# FreedomWingSMD.net
KiCad netlist of a schematic drawn in EAGLE
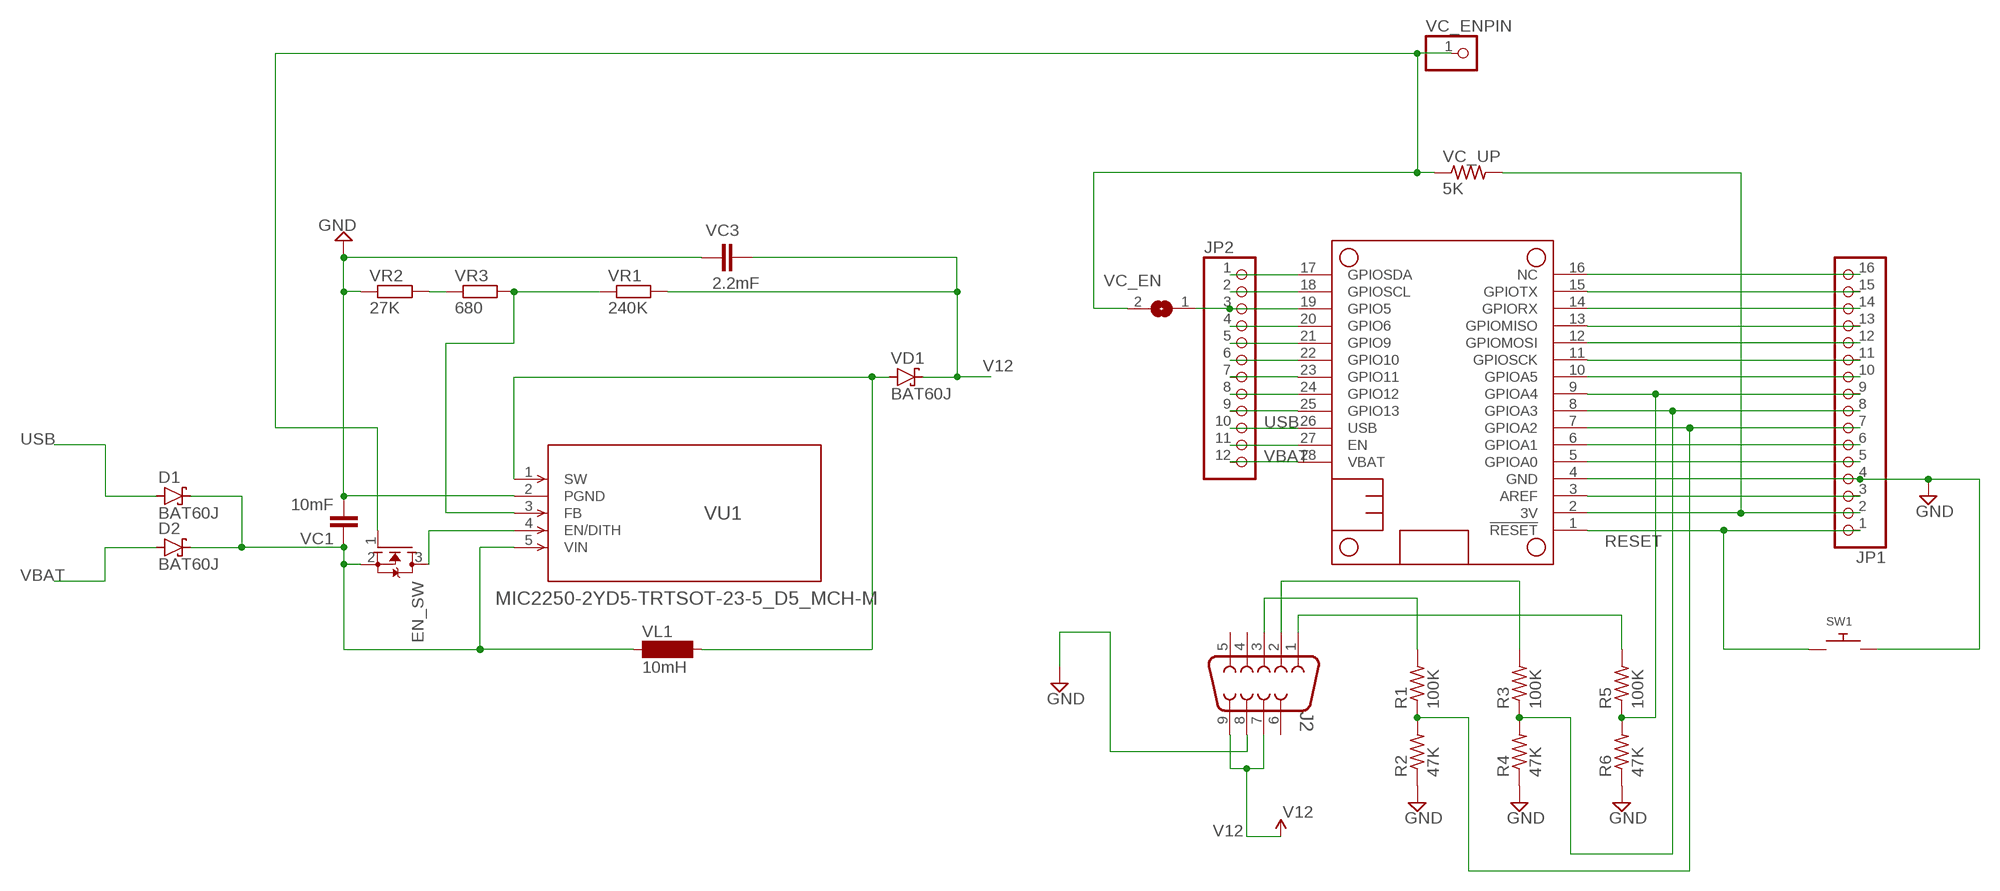
[diagram p0: schematic, sheet 1]

(export (version "E")
  (design (tool "Eeschema 10.0.6"))
  (components
    (comp (ref "D1")
      (value "BAT60J")
      (footprint "eagle-import:SOD323_ST")
      (libsource (lib "eagle-import") (part "BAT60J"))
    )
    (comp (ref "D2")
      (value "BAT60J")
      (footprint "eagle-import:SOD323_ST")
      (libsource (lib "eagle-import") (part "BAT60J"))
    )
    (comp (ref "EN_SW")
      (value "MOSFET-NREFLOW")
      (footprint "eagle-import:SOT23")
      (libsource (lib "eagle-import") (part "MOSFET-NREFLOW"))
    )
    (comp (ref "J2")
      (value "DB9MALE")
      (footprint "eagle-import:DB9_MALE")
      (libsource (lib "eagle-import") (part "DB9MALE"))
    )
    (comp (ref "JP1")
      (value "PINHD-1X16")
      (footprint "eagle-import:1X16")
      (libsource (lib "eagle-import") (part "PINHD-1X16"))
    )
    (comp (ref "JP2")
      (value "PINHD-1X12")
      (footprint "eagle-import:1X12")
      (libsource (lib "eagle-import") (part "PINHD-1X12"))
    )
    (comp (ref "MS1")
      (value "FEATHERWING_NODIM")
      (footprint "eagle-import:FEATHERWING_DIM")
      (libsource (lib "eagle-import") (part "FEATHERWING_NODIM"))
    )
    (comp (ref "R1")
      (value "100K")
      (footprint "eagle-import:R0805")
      (libsource (lib "eagle-import") (part "adafruit_420_R-US_R0805"))
    )
    (comp (ref "R2")
      (value "47K")
      (footprint "eagle-import:R0805")
      (libsource (lib "eagle-import") (part "adafruit_420_R-US_R0805"))
    )
    (comp (ref "R3")
      (value "100K")
      (footprint "eagle-import:R0805")
      (libsource (lib "eagle-import") (part "adafruit_420_R-US_R0805"))
    )
    (comp (ref "R4")
      (value "47K")
      (footprint "eagle-import:R0805")
      (libsource (lib "eagle-import") (part "adafruit_420_R-US_R0805"))
    )
    (comp (ref "R5")
      (value "100K")
      (footprint "eagle-import:R0805")
      (libsource (lib "eagle-import") (part "adafruit_420_R-US_R0805"))
    )
    (comp (ref "R6")
      (value "47K")
      (footprint "eagle-import:R0805")
      (libsource (lib "eagle-import") (part "adafruit_420_R-US_R0805"))
    )
    (comp (ref "SW1")
      (value "SWITCH_PUSHBUTTONC&K_KSS")
      (footprint "eagle-import:BTN_CK_KSS")
      (libsource (lib "eagle-import") (part "SWITCH_PUSHBUTTONC&K_KSS"))
    )
    (comp (ref "VC1")
      (value "10mF")
      (footprint "eagle-import:C0805")
      (libsource (lib "eagle-import") (part "C-EUC0805"))
    )
    (comp (ref "VC3")
      (value "2.2mF")
      (footprint "eagle-import:C0805")
      (libsource (lib "eagle-import") (part "C-EUC0805"))
    )
    (comp (ref "VC_EN")
      (value "SJW")
      (footprint "eagle-import:SJW")
      (libsource (lib "eagle-import") (part "SJW"))
    )
    (comp (ref "VC_ENPIN")
      (value "PINHD-1X1")
      (footprint "eagle-import:1X01")
      (libsource (lib "eagle-import") (part "PINHD-1X1"))
    )
    (comp (ref "VC_UP")
      (value "5K")
      (footprint "eagle-import:R0805")
      (libsource (lib "eagle-import") (part "R-US_R0805"))
    )
    (comp (ref "VD1")
      (value "BAT60J")
      (footprint "eagle-import:SOD323_ST")
      (libsource (lib "eagle-import") (part "BAT60J"))
    )
    (comp (ref "VL1")
      (value "10mH")
      (footprint "eagle-import:MS50")
      (libsource (lib "eagle-import") (part "MS50"))
    )
    (comp (ref "VR1")
      (value "240K")
      (footprint "eagle-import:R0805W")
      (libsource (lib "eagle-import") (part "R-EU_R0805W"))
    )
    (comp (ref "VR2")
      (value "27K")
      (footprint "eagle-import:R0805W")
      (libsource (lib "eagle-import") (part "R-EU_R0805W"))
    )
    (comp (ref "VR3")
      (value "680")
      (footprint "eagle-import:R0805W")
      (libsource (lib "eagle-import") (part "R-EU_R0805W"))
    )
    (comp (ref "VU1")
      (value "MIC2250-2YD5-TRTSOT-23-5_D5_MCH-M")
      (footprint "eagle-import:TSOT-23-5_D5_MCH-M")
      (fields
        (field (name "MANUFACTURER_PART_NUMBER") "MIC2250-2YD5-TR")
        (field (name "COPYRIGHT") "Copyright (C) 2018 Accelerated Designs. All rights reserved")
      )
      (libsource (lib "eagle-import") (part "MIC2250-2YD5-TRTSOT-23-5_D5_MCH-M"))
    )
  )
  (nets
    (net (code "1") (name "/RESET") (class "Default")
      (node (ref "JP1") (pin "1") (pinfunction "1_1") (pintype "passive"))
      (node (ref "MS1") (pin "1") (pinfunction "~{RESET}_1") (pintype "input"))
      (node (ref "SW1") (pin "P$1") (pinfunction "P$1_P$1") (pintype "passive"))
    )
    (net (code "2") (name "/USB") (class "Default")
      (node (ref "D1") (pin "A") (pinfunction "A_A") (pintype "passive"))
      (node (ref "JP2") (pin "10") (pinfunction "10_10") (pintype "passive"))
      (node (ref "MS1") (pin "26") (pinfunction "USB_26") (pintype "power_in"))
    )
    (net (code "3") (name "/VBAT") (class "Default")
      (node (ref "D2") (pin "A") (pinfunction "A_A") (pintype "passive"))
      (node (ref "JP2") (pin "12") (pinfunction "12_12") (pintype "passive"))
      (node (ref "MS1") (pin "28") (pinfunction "VBAT_28") (pintype "power_in"))
    )
    (net (code "4") (name "GND") (class "Default")
      (node (ref "J2") (pin "8") (pinfunction "8_8") (pintype "passive"))
      (node (ref "JP1") (pin "4") (pinfunction "4_4") (pintype "passive"))
      (node (ref "MS1") (pin "4") (pinfunction "GND_4") (pintype "power_in"))
      (node (ref "R2") (pin "1") (pinfunction "1_1") (pintype "passive"))
      (node (ref "R4") (pin "1") (pinfunction "1_1") (pintype "passive"))
      (node (ref "R6") (pin "1") (pinfunction "1_1") (pintype "passive"))
      (node (ref "SW1") (pin "P$2") (pinfunction "P$2_P$2") (pintype "passive"))
      (node (ref "VC1") (pin "2") (pinfunction "2_2") (pintype "passive"))
      (node (ref "VC3") (pin "1") (pinfunction "1_1") (pintype "passive"))
      (node (ref "VR2") (pin "1") (pinfunction "1_1") (pintype "passive"))
      (node (ref "VU1") (pin "2") (pinfunction "PGND_2") (pintype "power_in"))
    )
    (net (code "5") (name "Net-(EN_SW-D)") (class "Default")
      (node (ref "EN_SW") (pin "3") (pinfunction "D_3") (pintype "bidirectional"))
      (node (ref "VU1") (pin "4") (pinfunction "EN/DITH_4") (pintype "input"))
    )
    (net (code "6") (name "Net-(EN_SW-G)") (class "Default")
      (node (ref "EN_SW") (pin "1") (pinfunction "G_1") (pintype "bidirectional"))
      (node (ref "VC_EN") (pin "2") (pinfunction "2_2") (pintype "passive"))
      (node (ref "VC_ENPIN") (pin "1") (pinfunction "1_1") (pintype "passive"))
      (node (ref "VC_UP") (pin "1") (pinfunction "1_1") (pintype "passive"))
    )
    (net (code "7") (name "Net-(EN_SW-S)") (class "Default")
      (node (ref "D1") (pin "C") (pinfunction "C_C") (pintype "passive"))
      (node (ref "D2") (pin "C") (pinfunction "C_C") (pintype "passive"))
      (node (ref "EN_SW") (pin "2") (pinfunction "S_2") (pintype "bidirectional"))
      (node (ref "VC1") (pin "1") (pinfunction "1_1") (pintype "passive"))
      (node (ref "VL1") (pin "1") (pinfunction "1_1") (pintype "passive"))
      (node (ref "VU1") (pin "5") (pinfunction "VIN_5") (pintype "input"))
    )
    (net (code "8") (name "Net-(J2-Pad1)") (class "Default")
      (node (ref "J2") (pin "1") (pinfunction "1_1") (pintype "passive"))
      (node (ref "R5") (pin "2") (pinfunction "2_2") (pintype "passive"))
    )
    (net (code "9") (name "Net-(J2-Pad2)") (class "Default")
      (node (ref "J2") (pin "2") (pinfunction "2_2") (pintype "passive"))
      (node (ref "R3") (pin "2") (pinfunction "2_2") (pintype "passive"))
    )
    (net (code "10") (name "Net-(J2-Pad3)") (class "Default")
      (node (ref "J2") (pin "3") (pinfunction "3_3") (pintype "passive"))
      (node (ref "R1") (pin "2") (pinfunction "2_2") (pintype "passive"))
    )
    (net (code "11") (name "Net-(MS1-3V)") (class "Default")
      (node (ref "JP1") (pin "2") (pinfunction "2_2") (pintype "passive"))
      (node (ref "MS1") (pin "2") (pinfunction "3V_2") (pintype "power_in"))
      (node (ref "VC_UP") (pin "2") (pinfunction "2_2") (pintype "passive"))
    )
    (net (code "12") (name "Net-(MS1-AREF)") (class "Default")
      (node (ref "JP1") (pin "3") (pinfunction "3_3") (pintype "passive"))
      (node (ref "MS1") (pin "3") (pinfunction "AREF_3") (pintype "passive"))
    )
    (net (code "13") (name "Net-(MS1-EN)") (class "Default")
      (node (ref "JP2") (pin "11") (pinfunction "11_11") (pintype "passive"))
      (node (ref "MS1") (pin "27") (pinfunction "EN_27") (pintype "passive"))
    )
    (net (code "14") (name "Net-(MS1-GPIO5)") (class "Default")
      (node (ref "JP2") (pin "3") (pinfunction "3_3") (pintype "passive"))
      (node (ref "MS1") (pin "19") (pinfunction "GPIO5_19") (pintype "bidirectional"))
      (node (ref "VC_EN") (pin "1") (pinfunction "1_1") (pintype "passive"))
    )
    (net (code "15") (name "Net-(MS1-GPIO6)") (class "Default")
      (node (ref "JP2") (pin "4") (pinfunction "4_4") (pintype "passive"))
      (node (ref "MS1") (pin "20") (pinfunction "GPIO6_20") (pintype "bidirectional"))
    )
    (net (code "16") (name "Net-(MS1-GPIO9)") (class "Default")
      (node (ref "JP2") (pin "5") (pinfunction "5_5") (pintype "passive"))
      (node (ref "MS1") (pin "21") (pinfunction "GPIO9_21") (pintype "bidirectional"))
    )
    (net (code "17") (name "Net-(MS1-GPIO10)") (class "Default")
      (node (ref "JP2") (pin "6") (pinfunction "6_6") (pintype "passive"))
      (node (ref "MS1") (pin "22") (pinfunction "GPIO10_22") (pintype "bidirectional"))
    )
    (net (code "18") (name "Net-(MS1-GPIO11)") (class "Default")
      (node (ref "JP2") (pin "7") (pinfunction "7_7") (pintype "passive"))
      (node (ref "MS1") (pin "23") (pinfunction "GPIO11_23") (pintype "bidirectional"))
    )
    (net (code "19") (name "Net-(MS1-GPIO12)") (class "Default")
      (node (ref "JP2") (pin "8") (pinfunction "8_8") (pintype "passive"))
      (node (ref "MS1") (pin "24") (pinfunction "GPIO12_24") (pintype "bidirectional"))
    )
    (net (code "20") (name "Net-(MS1-GPIO13)") (class "Default")
      (node (ref "JP2") (pin "9") (pinfunction "9_9") (pintype "passive"))
      (node (ref "MS1") (pin "25") (pinfunction "GPIO13_25") (pintype "bidirectional"))
    )
    (net (code "21") (name "Net-(MS1-GPIOA0)") (class "Default")
      (node (ref "JP1") (pin "5") (pinfunction "5_5") (pintype "passive"))
      (node (ref "MS1") (pin "5") (pinfunction "GPIOA0_5") (pintype "bidirectional"))
    )
    (net (code "22") (name "Net-(MS1-GPIOA1)") (class "Default")
      (node (ref "JP1") (pin "6") (pinfunction "6_6") (pintype "passive"))
      (node (ref "MS1") (pin "6") (pinfunction "GPIOA1_6") (pintype "bidirectional"))
    )
    (net (code "23") (name "Net-(MS1-GPIOA2)") (class "Default")
      (node (ref "JP1") (pin "7") (pinfunction "7_7") (pintype "passive"))
      (node (ref "MS1") (pin "7") (pinfunction "GPIOA2_7") (pintype "bidirectional"))
      (node (ref "R1") (pin "1") (pinfunction "1_1") (pintype "passive"))
      (node (ref "R2") (pin "2") (pinfunction "2_2") (pintype "passive"))
    )
    (net (code "24") (name "Net-(MS1-GPIOA3)") (class "Default")
      (node (ref "JP1") (pin "8") (pinfunction "8_8") (pintype "passive"))
      (node (ref "MS1") (pin "8") (pinfunction "GPIOA3_8") (pintype "bidirectional"))
      (node (ref "R3") (pin "1") (pinfunction "1_1") (pintype "passive"))
      (node (ref "R4") (pin "2") (pinfunction "2_2") (pintype "passive"))
    )
    (net (code "25") (name "Net-(MS1-GPIOA4)") (class "Default")
      (node (ref "JP1") (pin "9") (pinfunction "9_9") (pintype "passive"))
      (node (ref "MS1") (pin "9") (pinfunction "GPIOA4_9") (pintype "bidirectional"))
      (node (ref "R5") (pin "1") (pinfunction "1_1") (pintype "passive"))
      (node (ref "R6") (pin "2") (pinfunction "2_2") (pintype "passive"))
    )
    (net (code "26") (name "Net-(MS1-GPIOA5)") (class "Default")
      (node (ref "JP1") (pin "10") (pinfunction "10_10") (pintype "passive"))
      (node (ref "MS1") (pin "10") (pinfunction "GPIOA5_10") (pintype "bidirectional"))
    )
    (net (code "27") (name "Net-(MS1-GPIOMISO)") (class "Default")
      (node (ref "JP1") (pin "13") (pinfunction "13_13") (pintype "passive"))
      (node (ref "MS1") (pin "13") (pinfunction "GPIOMISO_13") (pintype "bidirectional"))
    )
    (net (code "28") (name "Net-(MS1-GPIOMOSI)") (class "Default")
      (node (ref "JP1") (pin "12") (pinfunction "12_12") (pintype "passive"))
      (node (ref "MS1") (pin "12") (pinfunction "GPIOMOSI_12") (pintype "bidirectional"))
    )
    (net (code "29") (name "Net-(MS1-GPIORX)") (class "Default")
      (node (ref "JP1") (pin "14") (pinfunction "14_14") (pintype "passive"))
      (node (ref "MS1") (pin "14") (pinfunction "GPIORX_14") (pintype "bidirectional"))
    )
    (net (code "30") (name "Net-(MS1-GPIOSCK)") (class "Default")
      (node (ref "JP1") (pin "11") (pinfunction "11_11") (pintype "passive"))
      (node (ref "MS1") (pin "11") (pinfunction "GPIOSCK_11") (pintype "bidirectional"))
    )
    (net (code "31") (name "Net-(MS1-GPIOSCL)") (class "Default")
      (node (ref "JP2") (pin "2") (pinfunction "2_2") (pintype "passive"))
      (node (ref "MS1") (pin "18") (pinfunction "GPIOSCL_18") (pintype "bidirectional"))
    )
    (net (code "32") (name "Net-(MS1-GPIOSDA)") (class "Default")
      (node (ref "JP2") (pin "1") (pinfunction "1_1") (pintype "passive"))
      (node (ref "MS1") (pin "17") (pinfunction "GPIOSDA_17") (pintype "bidirectional"))
    )
    (net (code "33") (name "Net-(MS1-GPIOTX)") (class "Default")
      (node (ref "JP1") (pin "15") (pinfunction "15_15") (pintype "passive"))
      (node (ref "MS1") (pin "15") (pinfunction "GPIOTX_15") (pintype "bidirectional"))
    )
    (net (code "34") (name "Net-(MS1-NC)") (class "Default")
      (node (ref "JP1") (pin "16") (pinfunction "16_16") (pintype "passive"))
      (node (ref "MS1") (pin "16") (pinfunction "NC_16") (pintype "passive"))
    )
    (net (code "35") (name "Net-(VR2-Pad2)") (class "Default")
      (node (ref "VR2") (pin "2") (pinfunction "2_2") (pintype "passive"))
      (node (ref "VR3") (pin "1") (pinfunction "1_1") (pintype "passive"))
    )
    (net (code "36") (name "Net-(VU1-FB)") (class "Default")
      (node (ref "VR1") (pin "1") (pinfunction "1_1") (pintype "passive"))
      (node (ref "VR3") (pin "2") (pinfunction "2_2") (pintype "passive"))
      (node (ref "VU1") (pin "3") (pinfunction "FB_3") (pintype "input"))
    )
    (net (code "37") (name "Net-(VU1-SW)") (class "Default")
      (node (ref "VD1") (pin "A") (pinfunction "A_A") (pintype "passive"))
      (node (ref "VL1") (pin "2") (pinfunction "2_2") (pintype "passive"))
      (node (ref "VU1") (pin "1") (pinfunction "SW_1") (pintype "input"))
    )
    (net (code "38") (name "V12") (class "Default")
      (node (ref "J2") (pin "7") (pinfunction "7_7") (pintype "passive"))
      (node (ref "J2") (pin "9") (pinfunction "9_9") (pintype "passive"))
      (node (ref "VC3") (pin "2") (pinfunction "2_2") (pintype "passive"))
      (node (ref "VD1") (pin "C") (pinfunction "C_C") (pintype "passive"))
      (node (ref "VR1") (pin "2") (pinfunction "2_2") (pintype "passive"))
    )
    (net (code "39") (name "unconnected-(J2-Pad4)") (class "Default")
      (node (ref "J2") (pin "4") (pinfunction "4_4") (pintype "passive"))
    )
    (net (code "40") (name "unconnected-(J2-Pad5)") (class "Default")
      (node (ref "J2") (pin "5") (pinfunction "5_5") (pintype "passive"))
    )
    (net (code "41") (name "unconnected-(J2-Pad6)") (class "Default")
      (node (ref "J2") (pin "6") (pinfunction "6_6") (pintype "passive"))
    )
  )
)
